# Button_Board.net
KiCad netlist of a schematic drawn in EAGLE
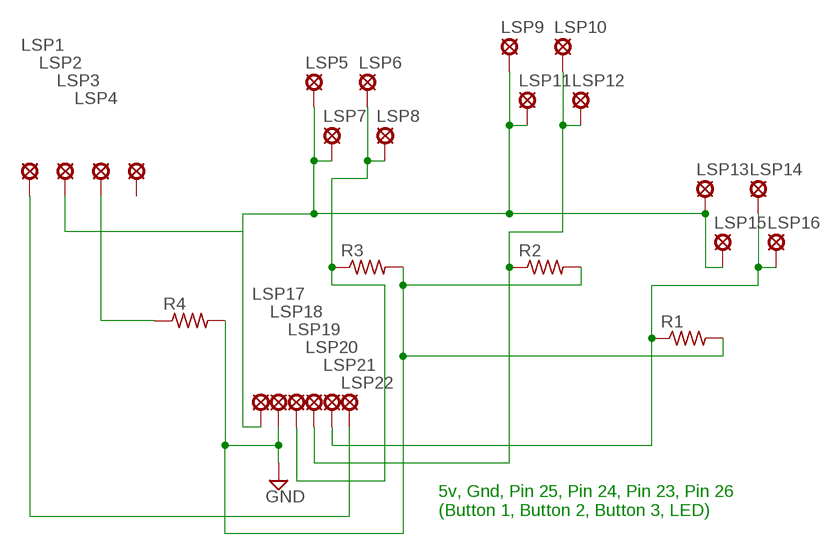
[diagram p0: schematic, sheet 1]

(export (version "E")
  (design (tool "Eeschema 10.0.6"))
  (components
    (comp (ref "LSP1")
      (value "LSP10_CLSP10_C")
      (footprint "eagle-import:LSP10_C")
      (libsource (lib "eagle-import") (part "LSP10_CLSP10_C"))
    )
    (comp (ref "LSP2")
      (value "LSP10_CLSP10_C")
      (footprint "eagle-import:LSP10_C")
      (libsource (lib "eagle-import") (part "LSP10_CLSP10_C"))
    )
    (comp (ref "LSP3")
      (value "LSP10_CLSP10_C")
      (footprint "eagle-import:LSP10_C")
      (libsource (lib "eagle-import") (part "LSP10_CLSP10_C"))
    )
    (comp (ref "LSP4")
      (value "LSP10_CLSP10_C")
      (footprint "eagle-import:LSP10_C")
      (libsource (lib "eagle-import") (part "LSP10_CLSP10_C"))
    )
    (comp (ref "LSP5")
      (value "LSP10_CLSP10_C")
      (footprint "eagle-import:LSP10_C")
      (libsource (lib "eagle-import") (part "LSP10_CLSP10_C"))
    )
    (comp (ref "LSP6")
      (value "LSP10_CLSP10_C")
      (footprint "eagle-import:LSP10_C")
      (libsource (lib "eagle-import") (part "LSP10_CLSP10_C"))
    )
    (comp (ref "LSP7")
      (value "LSP10_CLSP10_C")
      (footprint "eagle-import:LSP10_C")
      (libsource (lib "eagle-import") (part "LSP10_CLSP10_C"))
    )
    (comp (ref "LSP8")
      (value "LSP10_CLSP10_C")
      (footprint "eagle-import:LSP10_C")
      (libsource (lib "eagle-import") (part "LSP10_CLSP10_C"))
    )
    (comp (ref "LSP9")
      (value "LSP10_CLSP10_C")
      (footprint "eagle-import:LSP10_C")
      (libsource (lib "eagle-import") (part "LSP10_CLSP10_C"))
    )
    (comp (ref "LSP10")
      (value "LSP10_CLSP10_C")
      (footprint "eagle-import:LSP10_C")
      (libsource (lib "eagle-import") (part "LSP10_CLSP10_C"))
    )
    (comp (ref "LSP11")
      (value "LSP10_CLSP10_C")
      (footprint "eagle-import:LSP10_C")
      (libsource (lib "eagle-import") (part "LSP10_CLSP10_C"))
    )
    (comp (ref "LSP12")
      (value "LSP10_CLSP10_C")
      (footprint "eagle-import:LSP10_C")
      (libsource (lib "eagle-import") (part "LSP10_CLSP10_C"))
    )
    (comp (ref "LSP13")
      (value "LSP10_CLSP10_C")
      (footprint "eagle-import:LSP10_C")
      (libsource (lib "eagle-import") (part "LSP10_CLSP10_C"))
    )
    (comp (ref "LSP14")
      (value "LSP10_CLSP10_C")
      (footprint "eagle-import:LSP10_C")
      (libsource (lib "eagle-import") (part "LSP10_CLSP10_C"))
    )
    (comp (ref "LSP15")
      (value "LSP10_CLSP10_C")
      (footprint "eagle-import:LSP10_C")
      (libsource (lib "eagle-import") (part "LSP10_CLSP10_C"))
    )
    (comp (ref "LSP16")
      (value "LSP10_CLSP10_C")
      (footprint "eagle-import:LSP10_C")
      (libsource (lib "eagle-import") (part "LSP10_CLSP10_C"))
    )
    (comp (ref "LSP17")
      (value "LSP10_CLSP10_C")
      (footprint "eagle-import:LSP10_C")
      (libsource (lib "eagle-import") (part "LSP10_CLSP10_C"))
    )
    (comp (ref "LSP18")
      (value "LSP10_CLSP10_C")
      (footprint "eagle-import:LSP10_C")
      (libsource (lib "eagle-import") (part "LSP10_CLSP10_C"))
    )
    (comp (ref "LSP19")
      (value "LSP10_CLSP10_C")
      (footprint "eagle-import:LSP10_C")
      (libsource (lib "eagle-import") (part "LSP10_CLSP10_C"))
    )
    (comp (ref "LSP20")
      (value "LSP10_CLSP10_C")
      (footprint "eagle-import:LSP10_C")
      (libsource (lib "eagle-import") (part "LSP10_CLSP10_C"))
    )
    (comp (ref "LSP21")
      (value "LSP10_CLSP10_C")
      (footprint "eagle-import:LSP10_C")
      (libsource (lib "eagle-import") (part "LSP10_CLSP10_C"))
    )
    (comp (ref "LSP22")
      (value "LSP10_CLSP10_C")
      (footprint "eagle-import:LSP10_C")
      (libsource (lib "eagle-import") (part "LSP10_CLSP10_C"))
    )
    (comp (ref "R1")
      (value "R-US_VMTA55")
      (footprint "eagle-import:VMTA55")
      (libsource (lib "eagle-import") (part "R-US_VMTA55"))
    )
    (comp (ref "R2")
      (value "R-US_VMTA55")
      (footprint "eagle-import:VMTA55")
      (libsource (lib "eagle-import") (part "R-US_VMTA55"))
    )
    (comp (ref "R3")
      (value "R-US_VMTA55")
      (footprint "eagle-import:VMTA55")
      (libsource (lib "eagle-import") (part "R-US_VMTA55"))
    )
    (comp (ref "R4")
      (value "R-US_VMTA55")
      (footprint "eagle-import:VMTA55")
      (libsource (lib "eagle-import") (part "R-US_VMTA55"))
    )
  )
  (nets
    (net (code "1") (name "GND") (class "Default")
      (node (ref "LSP18") (pin "P$1") (pinfunction "MP_P$1") (pintype "passive"))
      (node (ref "R1") (pin "2") (pinfunction "2_2") (pintype "passive"))
      (node (ref "R2") (pin "2") (pinfunction "2_2") (pintype "passive"))
      (node (ref "R3") (pin "2") (pinfunction "2_2") (pintype "passive"))
      (node (ref "R4") (pin "2") (pinfunction "2_2") (pintype "passive"))
    )
    (net (code "2") (name "Net-(LSP1-MP)") (class "Default")
      (node (ref "LSP1") (pin "P$1") (pinfunction "MP_P$1") (pintype "passive"))
      (node (ref "LSP22") (pin "P$1") (pinfunction "MP_P$1") (pintype "passive"))
    )
    (net (code "3") (name "Net-(LSP3-MP)") (class "Default")
      (node (ref "LSP3") (pin "P$1") (pinfunction "MP_P$1") (pintype "passive"))
      (node (ref "R4") (pin "1") (pinfunction "1_1") (pintype "passive"))
    )
    (net (code "4") (name "Net-(LSP10-MP)") (class "Default")
      (node (ref "LSP10") (pin "P$1") (pinfunction "MP_P$1") (pintype "passive"))
      (node (ref "LSP12") (pin "P$1") (pinfunction "MP_P$1") (pintype "passive"))
      (node (ref "LSP20") (pin "P$1") (pinfunction "MP_P$1") (pintype "passive"))
      (node (ref "R2") (pin "1") (pinfunction "1_1") (pintype "passive"))
    )
    (net (code "5") (name "Net-(LSP11-MP)") (class "Default")
      (node (ref "LSP11") (pin "P$1") (pinfunction "MP_P$1") (pintype "passive"))
      (node (ref "LSP13") (pin "P$1") (pinfunction "MP_P$1") (pintype "passive"))
      (node (ref "LSP15") (pin "P$1") (pinfunction "MP_P$1") (pintype "passive"))
      (node (ref "LSP17") (pin "P$1") (pinfunction "MP_P$1") (pintype "passive"))
      (node (ref "LSP2") (pin "P$1") (pinfunction "MP_P$1") (pintype "passive"))
      (node (ref "LSP5") (pin "P$1") (pinfunction "MP_P$1") (pintype "passive"))
      (node (ref "LSP7") (pin "P$1") (pinfunction "MP_P$1") (pintype "passive"))
      (node (ref "LSP9") (pin "P$1") (pinfunction "MP_P$1") (pintype "passive"))
    )
    (net (code "6") (name "Net-(LSP14-MP)") (class "Default")
      (node (ref "LSP14") (pin "P$1") (pinfunction "MP_P$1") (pintype "passive"))
      (node (ref "LSP16") (pin "P$1") (pinfunction "MP_P$1") (pintype "passive"))
      (node (ref "LSP21") (pin "P$1") (pinfunction "MP_P$1") (pintype "passive"))
      (node (ref "R1") (pin "1") (pinfunction "1_1") (pintype "passive"))
    )
    (net (code "7") (name "Net-(LSP19-MP)") (class "Default")
      (node (ref "LSP19") (pin "P$1") (pinfunction "MP_P$1") (pintype "passive"))
      (node (ref "LSP6") (pin "P$1") (pinfunction "MP_P$1") (pintype "passive"))
      (node (ref "LSP8") (pin "P$1") (pinfunction "MP_P$1") (pintype "passive"))
      (node (ref "R3") (pin "1") (pinfunction "1_1") (pintype "passive"))
    )
    (net (code "8") (name "unconnected-(LSP4-MP-PadP$1)") (class "Default")
      (node (ref "LSP4") (pin "P$1") (pinfunction "MP_P$1") (pintype "passive"))
    )
  )
)
